# diff_probe.net
KiCad netlist of a schematic drawn in Altium Designer
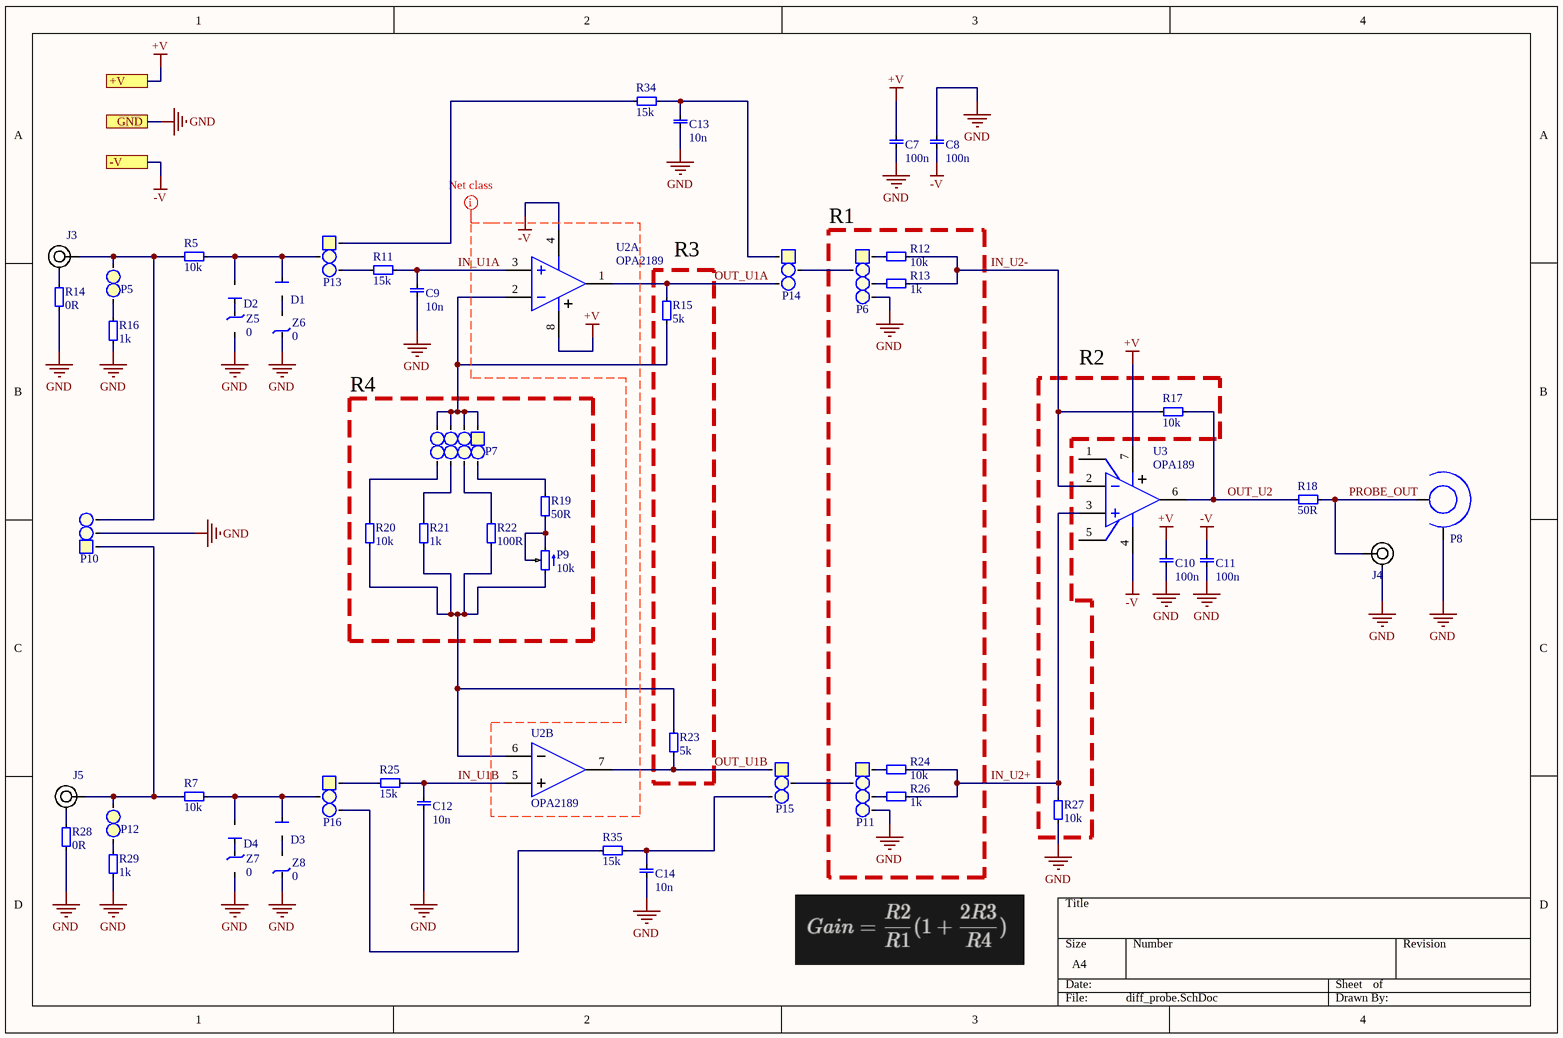
[diagram p0: diff_probe.SchDoc]

(export (version "E")
  (design (tool "Eeschema 10.0.6"))
  (components
    (comp (ref "C7")
      (value "100n")
      (footprint "0603 cap")
      (fields (field (name "Comment") "0603, capacitor"))
      (libsource (lib "jclib") (part "0603, capacitor"))
    )
    (comp (ref "C8")
      (value "100n")
      (footprint "0603 cap")
      (fields (field (name "Comment") "0603, capacitor"))
      (libsource (lib "jclib") (part "0603, capacitor"))
    )
    (comp (ref "C9")
      (value "10n")
      (footprint "0603 cap")
      (fields (field (name "Comment") "0603, capacitor"))
      (libsource (lib "jclib") (part "0603, capacitor"))
    )
    (comp (ref "C10")
      (value "100n")
      (footprint "0603 cap")
      (fields (field (name "Comment") "0603, capacitor"))
      (libsource (lib "jclib") (part "0603, capacitor"))
    )
    (comp (ref "C11")
      (value "100n")
      (footprint "0603 cap")
      (fields (field (name "Comment") "0603, capacitor"))
      (libsource (lib "jclib") (part "0603, capacitor"))
    )
    (comp (ref "C12")
      (value "10n")
      (footprint "0603 cap")
      (fields (field (name "Comment") "0603, capacitor"))
      (libsource (lib "jclib") (part "0603, capacitor"))
    )
    (comp (ref "C13")
      (value "10n")
      (footprint "0603 cap")
      (fields (field (name "Comment") "0603, capacitor"))
      (libsource (lib "jclib") (part "0603, capacitor"))
    )
    (comp (ref "C14")
      (value "10n")
      (footprint "0603 cap")
      (fields (field (name "Comment") "0603, capacitor"))
      (libsource (lib "jclib") (part "0603, capacitor"))
    )
    (comp (ref "D1") (value "Diode, SMD") (footprint "SOD323") (libsource (lib "jclib") (part "Diode, SMD")))
    (comp (ref "D2") (value "Diode, SMD") (footprint "SOD323") (libsource (lib "jclib") (part "Diode, SMD")))
    (comp (ref "D3") (value "Diode, SMD") (footprint "SOD323") (libsource (lib "jclib") (part "Diode, SMD")))
    (comp (ref "D4") (value "Diode, SMD") (footprint "SOD323") (libsource (lib "jclib") (part "Diode, SMD")))
    (comp (ref "J3")
      (value "SMA H")
      (footprint "EMPCB.SMAFSTJ.C.HT")
      (libsource (lib "jclib") (part "SMA H"))
    )
    (comp (ref "J4")
      (value "SMA H")
      (footprint "EMPCB.SMAFSTJ.C.HT")
      (libsource (lib "jclib") (part "SMA H"))
    )
    (comp (ref "J5")
      (value "SMA H")
      (footprint "EMPCB.SMAFSTJ.C.HT")
      (libsource (lib "jclib") (part "SMA H"))
    )
    (comp (ref "P5")
      (value "1x2 Pin Heade Straight")
      (footprint "padtwo_L")
      (description "2.54 mm, TH")
      (libsource (lib "jclib") (part "1x2 Pin Heade Straight"))
    )
    (comp (ref "P6")
      (value "4x1 Pin Header")
      (footprint "padFour_L")
      (description "2.54 mm")
      (libsource (lib "jclib") (part "1x4 Pin Header MUX"))
    )
    (comp (ref "P7")
      (value "2x4 Pin Header")
      (footprint "2X4 PH")
      (description "2.54mm,")
      (libsource (lib "jclib") (part "2x4 Pin Header"))
    )
    (comp (ref "P8")
      (value "BNC connector")
      (footprint "BNC_con")
      (libsource (lib "jclib") (part "BNC connector"))
    )
    (comp (ref "P9")
      (value "10k")
      (footprint "PV36W104C01B00")
      (fields (field (name "Comment") "Pot"))
      (libsource (lib "jclib") (part "Pot"))
    )
    (comp (ref "P10")
      (value "1x3 Pin Header")
      (footprint "1x3_horizontal")
      (description "2.54 mm")
      (libsource (lib "jclib") (part "1x3 Pin Header"))
    )
    (comp (ref "P11")
      (value "4x1 Pin Header")
      (footprint "padFour_L")
      (description "2.54 mm")
      (libsource (lib "jclib") (part "1x4 Pin Header MUX"))
    )
    (comp (ref "P12")
      (value "1x2 Pin Heade Straight")
      (footprint "padtwo_L")
      (description "2.54 mm, TH")
      (libsource (lib "jclib") (part "1x2 Pin Heade Straight"))
    )
    (comp (ref "P13")
      (value "1x3 Pin Header Mux")
      (footprint "padThree_L")
      (description "2.54 mm")
      (libsource (lib "jclib") (part "1x3 Pin Header Mux"))
    )
    (comp (ref "P14")
      (value "1x3 Pin Header Mux")
      (footprint "padThree_L")
      (description "2.54 mm")
      (libsource (lib "") (part "1x3 Pin Header Mux_1"))
    )
    (comp (ref "P15")
      (value "1x3 Pin Header Mux")
      (footprint "padThree_L")
      (description "2.54 mm")
      (libsource (lib "") (part "1x3 Pin Header Mux_1"))
    )
    (comp (ref "P16")
      (value "1x3 Pin Header Mux")
      (footprint "padThree_L")
      (description "2.54 mm")
      (libsource (lib "jclib") (part "1x3 Pin Header Mux"))
    )
    (comp (ref "R5")
      (value "10k")
      (footprint "2512, res")
      (fields (field (name "Comment") "2512, resistor"))
      (libsource (lib "jclib") (part "2512, resistor"))
    )
    (comp (ref "R7")
      (value "10k")
      (footprint "2512, res")
      (fields (field (name "Comment") "2512, resistor"))
      (libsource (lib "jclib") (part "2512, resistor"))
    )
    (comp (ref "R11")
      (value "15k")
      (footprint "0603")
      (fields (field (name "Comment") "0603, resistor"))
      (libsource (lib "jclib") (part "0603, resistor"))
    )
    (comp (ref "R12")
      (value "10k")
      (footprint "0603")
      (fields (field (name "Comment") "0603, resistor"))
      (libsource (lib "jclib") (part "0603, resistor"))
    )
    (comp (ref "R13")
      (value "1k")
      (footprint "0603")
      (fields (field (name "Comment") "0603, resistor"))
      (libsource (lib "jclib") (part "0603, resistor"))
    )
    (comp (ref "R14")
      (value "0R")
      (footprint "0603")
      (fields (field (name "Comment") "0603, resistor"))
      (libsource (lib "jclib") (part "0603, resistor"))
    )
    (comp (ref "R15")
      (value "5k")
      (footprint "0603")
      (fields (field (name "Comment") "0603, resistor"))
      (libsource (lib "jclib") (part "0603, resistor"))
    )
    (comp (ref "R16")
      (value "1k")
      (footprint "0603")
      (fields (field (name "Comment") "0603, resistor"))
      (libsource (lib "jclib") (part "0603, resistor"))
    )
    (comp (ref "R17")
      (value "10k")
      (footprint "0603")
      (fields (field (name "Comment") "0603, resistor"))
      (libsource (lib "jclib") (part "0603, resistor"))
    )
    (comp (ref "R18")
      (value "50R")
      (footprint "0603")
      (fields (field (name "Comment") "0603, resistor"))
      (libsource (lib "jclib") (part "0603, resistor"))
    )
    (comp (ref "R19")
      (value "50R")
      (footprint "0603")
      (fields (field (name "Comment") "0603, resistor"))
      (libsource (lib "jclib") (part "0603, resistor"))
    )
    (comp (ref "R20")
      (value "10k")
      (footprint "0603")
      (fields (field (name "Comment") "0603, resistor"))
      (libsource (lib "jclib") (part "0603, resistor"))
    )
    (comp (ref "R21")
      (value "1k")
      (footprint "0603")
      (fields (field (name "Comment") "0603, resistor"))
      (libsource (lib "jclib") (part "0603, resistor"))
    )
    (comp (ref "R22")
      (value "100R")
      (footprint "0603")
      (fields (field (name "Comment") "0603, resistor"))
      (libsource (lib "jclib") (part "0603, resistor"))
    )
    (comp (ref "R23")
      (value "5k")
      (footprint "0603")
      (fields (field (name "Comment") "0603, resistor"))
      (libsource (lib "jclib") (part "0603, resistor"))
    )
    (comp (ref "R24")
      (value "10k")
      (footprint "0603")
      (fields (field (name "Comment") "0603, resistor"))
      (libsource (lib "jclib") (part "0603, resistor"))
    )
    (comp (ref "R25")
      (value "15k")
      (footprint "0603")
      (fields (field (name "Comment") "0603, resistor"))
      (libsource (lib "jclib") (part "0603, resistor"))
    )
    (comp (ref "R26")
      (value "1k")
      (footprint "0603")
      (fields (field (name "Comment") "0603, resistor"))
      (libsource (lib "jclib") (part "0603, resistor"))
    )
    (comp (ref "R27")
      (value "10k")
      (footprint "0603")
      (fields (field (name "Comment") "0603, resistor"))
      (libsource (lib "jclib") (part "0603, resistor"))
    )
    (comp (ref "R28")
      (value "0R")
      (footprint "0603")
      (fields (field (name "Comment") "0603, resistor"))
      (libsource (lib "jclib") (part "0603, resistor"))
    )
    (comp (ref "R29")
      (value "1k")
      (footprint "0603")
      (fields (field (name "Comment") "0603, resistor"))
      (libsource (lib "jclib") (part "0603, resistor"))
    )
    (comp (ref "R34")
      (value "15k")
      (footprint "0603")
      (fields (field (name "Comment") "0603, resistor"))
      (libsource (lib "jclib") (part "0603, resistor"))
    )
    (comp (ref "R35")
      (value "15k")
      (footprint "0603")
      (fields (field (name "Comment") "0603, resistor"))
      (libsource (lib "jclib") (part "0603, resistor"))
    )
    (comp (ref "U2")
      (value "OPA2189")
      (footprint "SOIC8/SOT238")
      (description "Dual FET-Input Operational Amplifier")
      (libsource (lib "jclib") (part "MAX44251"))
    )
    (comp (ref "U3") (value "OPA189") (footprint "SOIC8") (libsource (lib "jclib") (part "TL071")))
    (comp (ref "Z5")
      (value "0")
      (footprint "SOT-23")
      (fields (field (name "Comment") "Zener BZX84"))
      (libsource (lib "jclib") (part "Zener BZX84"))
    )
    (comp (ref "Z6")
      (value "0")
      (footprint "SOT-23")
      (fields (field (name "Comment") "Zener BZX84"))
      (libsource (lib "jclib") (part "Zener BZX84"))
    )
    (comp (ref "Z7")
      (value "0")
      (footprint "SOT-23")
      (fields (field (name "Comment") "Zener BZX84"))
      (libsource (lib "jclib") (part "Zener BZX84"))
    )
    (comp (ref "Z8")
      (value "0")
      (footprint "SOT-23")
      (fields (field (name "Comment") "Zener BZX84"))
      (libsource (lib "jclib") (part "Zener BZX84"))
    )
  )
  (nets
    (net (code "1") (name "+V") (class "Default")
      (node (ref "C10") (pin "1") (pinfunction "1_1") (pintype "passive"))
      (node (ref "C7") (pin "1") (pinfunction "1_1") (pintype "passive"))
      (node (ref "U2") (pin "8") (pinfunction "V+_8") (pintype "power_in"))
      (node (ref "U3") (pin "7") (pinfunction "V+_7") (pintype "power_in"))
    )
    (net (code "2") (name "-V") (class "Default")
      (node (ref "C11") (pin "1") (pinfunction "1_1") (pintype "passive"))
      (node (ref "C8") (pin "1") (pinfunction "1_1") (pintype "passive"))
      (node (ref "U2") (pin "4") (pinfunction "V-_4") (pintype "power_in"))
      (node (ref "U3") (pin "4") (pinfunction "V-_4") (pintype "power_in"))
    )
    (net (code "3") (name "/IN_U1A") (class "Default")
      (node (ref "C9") (pin "1") (pinfunction "1_1") (pintype "passive"))
      (node (ref "R11") (pin "0") (pinfunction "0_0") (pintype "passive"))
      (node (ref "U2") (pin "3") (pinfunction "IN+_3") (pintype "passive"))
    )
    (net (code "4") (name "/IN_U1B") (class "Default")
      (node (ref "C12") (pin "1") (pinfunction "1_1") (pintype "passive"))
      (node (ref "R25") (pin "0") (pinfunction "0_0") (pintype "passive"))
      (node (ref "U2") (pin "5") (pinfunction "IN+_5") (pintype "passive"))
    )
    (net (code "5") (name "/IN_U2+") (class "Default")
      (node (ref "R24") (pin "0") (pinfunction "0_0") (pintype "passive"))
      (node (ref "R26") (pin "0") (pinfunction "0_0") (pintype "passive"))
      (node (ref "R27") (pin "0") (pinfunction "0_0") (pintype "passive"))
      (node (ref "U3") (pin "3") (pinfunction "IN+_3") (pintype "passive"))
    )
    (net (code "6") (name "/IN_U2-") (class "Default")
      (node (ref "R12") (pin "0") (pinfunction "0_0") (pintype "passive"))
      (node (ref "R13") (pin "0") (pinfunction "0_0") (pintype "passive"))
      (node (ref "R17") (pin "1") (pinfunction "1_1") (pintype "passive"))
      (node (ref "U3") (pin "2") (pinfunction "IN-_2") (pintype "passive"))
    )
    (net (code "7") (name "/OUT_U1A") (class "Default")
      (node (ref "P14") (pin "3") (pinfunction "3_3") (pintype "passive"))
      (node (ref "R15") (pin "1") (pinfunction "1_1") (pintype "passive"))
      (node (ref "U2") (pin "1") (pinfunction "OUT1_1") (pintype "passive"))
    )
    (net (code "8") (name "/OUT_U1B") (class "Default")
      (node (ref "P15") (pin "1") (pinfunction "1_1") (pintype "passive"))
      (node (ref "R23") (pin "0") (pinfunction "0_0") (pintype "passive"))
      (node (ref "U2") (pin "7") (pinfunction "OUT2_7") (pintype "passive"))
    )
    (net (code "9") (name "/OUT_U2") (class "Default")
      (node (ref "R17") (pin "0") (pinfunction "0_0") (pintype "passive"))
      (node (ref "R18") (pin "1") (pinfunction "1_1") (pintype "passive"))
      (node (ref "U3") (pin "6") (pinfunction "OUT_6") (pintype "passive"))
    )
    (net (code "10") (name "/PROBE_OUT") (class "Default")
      (node (ref "J4") (pin "2") (pinfunction "2_2") (pintype "passive"))
      (node (ref "P8") (pin "1") (pinfunction "1_1") (pintype "passive"))
      (node (ref "R18") (pin "0") (pinfunction "0_0") (pintype "passive"))
    )
    (net (code "11") (name "GND") (class "Default")
      (node (ref "C10") (pin "0") (pinfunction "0_0") (pintype "passive"))
      (node (ref "C11") (pin "0") (pinfunction "0_0") (pintype "passive"))
      (node (ref "C12") (pin "0") (pinfunction "0_0") (pintype "passive"))
      (node (ref "C13") (pin "0") (pinfunction "0_0") (pintype "passive"))
      (node (ref "C14") (pin "0") (pinfunction "0_0") (pintype "passive"))
      (node (ref "C7") (pin "0") (pinfunction "0_0") (pintype "passive"))
      (node (ref "C8") (pin "0") (pinfunction "0_0") (pintype "passive"))
      (node (ref "C9") (pin "0") (pinfunction "0_0") (pintype "passive"))
      (node (ref "J4") (pin "1") (pinfunction "1_1") (pintype "passive"))
      (node (ref "P10") (pin "2") (pinfunction "2_2") (pintype "passive"))
      (node (ref "P11") (pin "4") (pinfunction "4_4") (pintype "passive"))
      (node (ref "P6") (pin "4") (pinfunction "4_4") (pintype "passive"))
      (node (ref "P8") (pin "2") (pinfunction "2_2") (pintype "passive"))
      (node (ref "R14") (pin "1") (pinfunction "1_1") (pintype "passive"))
      (node (ref "R16") (pin "1") (pinfunction "1_1") (pintype "passive"))
      (node (ref "R27") (pin "1") (pinfunction "1_1") (pintype "passive"))
      (node (ref "R28") (pin "1") (pinfunction "1_1") (pintype "passive"))
      (node (ref "R29") (pin "1") (pinfunction "1_1") (pintype "passive"))
      (node (ref "Z5") (pin "1") (pinfunction "Anode_1") (pintype "passive"))
      (node (ref "Z6") (pin "3") (pinfunction "Cathode_3") (pintype "passive"))
      (node (ref "Z7") (pin "1") (pinfunction "Anode_1") (pintype "passive"))
      (node (ref "Z8") (pin "3") (pinfunction "Cathode_3") (pintype "passive"))
    )
    (net (code "12") (name "Net-(C13-Pad1)") (class "Default")
      (node (ref "C13") (pin "1") (pinfunction "1_1") (pintype "passive"))
      (node (ref "P14") (pin "1") (pinfunction "1_1") (pintype "passive"))
      (node (ref "R34") (pin "0") (pinfunction "0_0") (pintype "passive"))
    )
    (net (code "13") (name "Net-(C14-Pad1)") (class "Default")
      (node (ref "C14") (pin "1") (pinfunction "1_1") (pintype "passive"))
      (node (ref "P15") (pin "3") (pinfunction "3_3") (pintype "passive"))
      (node (ref "R35") (pin "0") (pinfunction "0_0") (pintype "passive"))
    )
    (net (code "14") (name "Net-(D1-Pad1)") (class "Default")
      (node (ref "D1") (pin "1") (pinfunction "1_1") (pintype "passive"))
      (node (ref "D2") (pin "2") (pinfunction "2_2") (pintype "passive"))
      (node (ref "P13") (pin "2") (pinfunction "2_2") (pintype "passive"))
      (node (ref "R5") (pin "1") (pinfunction "1_1") (pintype "passive"))
    )
    (net (code "15") (name "Net-(D3-Pad1)") (class "Default")
      (node (ref "D3") (pin "1") (pinfunction "1_1") (pintype "passive"))
      (node (ref "D4") (pin "2") (pinfunction "2_2") (pintype "passive"))
      (node (ref "P16") (pin "2") (pinfunction "2_2") (pintype "passive"))
      (node (ref "R7") (pin "1") (pinfunction "1_1") (pintype "passive"))
    )
    (net (code "16") (name "Net-(J3-Pad1)") (class "Default")
      (node (ref "J3") (pin "1") (pinfunction "1_1") (pintype "passive"))
      (node (ref "R14") (pin "0") (pinfunction "0_0") (pintype "passive"))
    )
    (net (code "17") (name "Net-(J3-Pad2)") (class "Default")
      (node (ref "J3") (pin "2") (pinfunction "2_2") (pintype "passive"))
      (node (ref "P10") (pin "3") (pinfunction "3_3") (pintype "passive"))
      (node (ref "P5") (pin "1") (pinfunction "1_1") (pintype "passive"))
      (node (ref "R5") (pin "0") (pinfunction "0_0") (pintype "passive"))
    )
    (net (code "18") (name "Net-(J5-Pad1)") (class "Default")
      (node (ref "J5") (pin "1") (pinfunction "1_1") (pintype "passive"))
      (node (ref "R28") (pin "0") (pinfunction "0_0") (pintype "passive"))
    )
    (net (code "19") (name "Net-(J5-Pad2)") (class "Default")
      (node (ref "J5") (pin "2") (pinfunction "2_2") (pintype "passive"))
      (node (ref "P10") (pin "1") (pinfunction "1_1") (pintype "passive"))
      (node (ref "P12") (pin "1") (pinfunction "1_1") (pintype "passive"))
      (node (ref "R7") (pin "0") (pinfunction "0_0") (pintype "passive"))
    )
    (net (code "20") (name "Net-(P5-Pad2)") (class "Default")
      (node (ref "P5") (pin "2") (pinfunction "2_2") (pintype "passive"))
      (node (ref "R16") (pin "0") (pinfunction "0_0") (pintype "passive"))
    )
    (net (code "21") (name "Net-(P6-Pad1)") (class "Default")
      (node (ref "P6") (pin "1") (pinfunction "1_1") (pintype "passive"))
      (node (ref "R12") (pin "1") (pinfunction "1_1") (pintype "passive"))
    )
    (net (code "22") (name "Net-(P6-Pad3)") (class "Default")
      (node (ref "P6") (pin "3") (pinfunction "3_3") (pintype "passive"))
      (node (ref "R13") (pin "1") (pinfunction "1_1") (pintype "passive"))
    )
    (net (code "23") (name "Net-(P7-Pad5)") (class "Default")
      (node (ref "P7") (pin "5") (pinfunction "5_5") (pintype "passive"))
      (node (ref "R20") (pin "1") (pinfunction "1_1") (pintype "passive"))
    )
    (net (code "24") (name "Net-(P7-Pad6)") (class "Default")
      (node (ref "P7") (pin "6") (pinfunction "6_6") (pintype "passive"))
      (node (ref "R21") (pin "1") (pinfunction "1_1") (pintype "passive"))
    )
    (net (code "25") (name "Net-(P7-Pad7)") (class "Default")
      (node (ref "P7") (pin "7") (pinfunction "7_7") (pintype "passive"))
      (node (ref "R22") (pin "1") (pinfunction "1_1") (pintype "passive"))
    )
    (net (code "26") (name "Net-(P7-Pad8)") (class "Default")
      (node (ref "P7") (pin "8") (pinfunction "8_8") (pintype "passive"))
      (node (ref "R19") (pin "1") (pinfunction "1_1") (pintype "passive"))
    )
    (net (code "27") (name "Net-(P9-Pad2)") (class "Default")
      (node (ref "P9") (pin "2") (pinfunction "2_2") (pintype "passive"))
      (node (ref "P9") (pin "3") (pinfunction "3_3") (pintype "passive"))
      (node (ref "R19") (pin "0") (pinfunction "0_0") (pintype "passive"))
    )
    (net (code "28") (name "Net-(P11-Pad1)") (class "Default")
      (node (ref "P11") (pin "1") (pinfunction "1_1") (pintype "passive"))
      (node (ref "R24") (pin "1") (pinfunction "1_1") (pintype "passive"))
    )
    (net (code "29") (name "Net-(P11-Pad2)") (class "Default")
      (node (ref "P11") (pin "2") (pinfunction "2_2") (pintype "passive"))
      (node (ref "P15") (pin "2") (pinfunction "2_2") (pintype "passive"))
    )
    (net (code "30") (name "Net-(P11-Pad3)") (class "Default")
      (node (ref "P11") (pin "3") (pinfunction "3_3") (pintype "passive"))
      (node (ref "R26") (pin "1") (pinfunction "1_1") (pintype "passive"))
    )
    (net (code "31") (name "Net-(P12-Pad2)") (class "Default")
      (node (ref "P12") (pin "2") (pinfunction "2_2") (pintype "passive"))
      (node (ref "R29") (pin "0") (pinfunction "0_0") (pintype "passive"))
    )
    (net (code "32") (name "Net-(P13-Pad1)") (class "Default")
      (node (ref "P13") (pin "1") (pinfunction "1_1") (pintype "passive"))
      (node (ref "R34") (pin "1") (pinfunction "1_1") (pintype "passive"))
    )
    (net (code "33") (name "Net-(P13-Pad3)") (class "Default")
      (node (ref "P13") (pin "3") (pinfunction "3_3") (pintype "passive"))
      (node (ref "R11") (pin "1") (pinfunction "1_1") (pintype "passive"))
    )
    (net (code "34") (name "Net-(P14-Pad2)") (class "Default")
      (node (ref "P14") (pin "2") (pinfunction "2_2") (pintype "passive"))
      (node (ref "P6") (pin "2") (pinfunction "2_2") (pintype "passive"))
    )
    (net (code "35") (name "Net-(P16-Pad1)") (class "Default")
      (node (ref "P16") (pin "1") (pinfunction "1_1") (pintype "passive"))
      (node (ref "R25") (pin "1") (pinfunction "1_1") (pintype "passive"))
    )
    (net (code "36") (name "Net-(P16-Pad3)") (class "Default")
      (node (ref "P16") (pin "3") (pinfunction "3_3") (pintype "passive"))
      (node (ref "R35") (pin "1") (pinfunction "1_1") (pintype "passive"))
    )
    (net (code "37") (name "Net-(U2A-IN-)") (class "Default")
      (node (ref "P7") (pin "1") (pinfunction "1_1") (pintype "passive"))
      (node (ref "P7") (pin "2") (pinfunction "2_2") (pintype "passive"))
      (node (ref "P7") (pin "3") (pinfunction "3_3") (pintype "passive"))
      (node (ref "P7") (pin "4") (pinfunction "4_4") (pintype "passive"))
      (node (ref "R15") (pin "0") (pinfunction "0_0") (pintype "passive"))
      (node (ref "U2") (pin "2") (pinfunction "IN-_2") (pintype "passive"))
    )
    (net (code "38") (name "Net-(U2B-IN-)") (class "Default")
      (node (ref "P9") (pin "1") (pinfunction "1_1") (pintype "passive"))
      (node (ref "R20") (pin "0") (pinfunction "0_0") (pintype "passive"))
      (node (ref "R21") (pin "0") (pinfunction "0_0") (pintype "passive"))
      (node (ref "R22") (pin "0") (pinfunction "0_0") (pintype "passive"))
      (node (ref "R23") (pin "1") (pinfunction "1_1") (pintype "passive"))
      (node (ref "U2") (pin "6") (pinfunction "IN-_6") (pintype "passive"))
    )
    (net (code "39") (name "Net-(Z5-Cathode)") (class "Default")
      (node (ref "D2") (pin "1") (pinfunction "1_1") (pintype "passive"))
      (node (ref "Z5") (pin "3") (pinfunction "Cathode_3") (pintype "passive"))
    )
    (net (code "40") (name "Net-(Z6-Anode)") (class "Default")
      (node (ref "D1") (pin "2") (pinfunction "2_2") (pintype "passive"))
      (node (ref "Z6") (pin "1") (pinfunction "Anode_1") (pintype "passive"))
    )
    (net (code "41") (name "Net-(Z7-Cathode)") (class "Default")
      (node (ref "D4") (pin "1") (pinfunction "1_1") (pintype "passive"))
      (node (ref "Z7") (pin "3") (pinfunction "Cathode_3") (pintype "passive"))
    )
    (net (code "42") (name "Net-(Z8-Anode)") (class "Default")
      (node (ref "D3") (pin "2") (pinfunction "2_2") (pintype "passive"))
      (node (ref "Z8") (pin "1") (pinfunction "Anode_1") (pintype "passive"))
    )
    (net (code "43") (name "unconnected-(U3-OS_TRIM-Pad1)") (class "Default")
      (node (ref "U3") (pin "1") (pinfunction "OS_TRIM_1") (pintype "passive"))
    )
    (net (code "44") (name "unconnected-(U3-OS_TRIM-Pad5)") (class "Default")
      (node (ref "U3") (pin "5") (pinfunction "OS_TRIM_5") (pintype "passive"))
    )
  )
)
